# MCU.net
KiCad netlist of a schematic drawn in Altium Designer
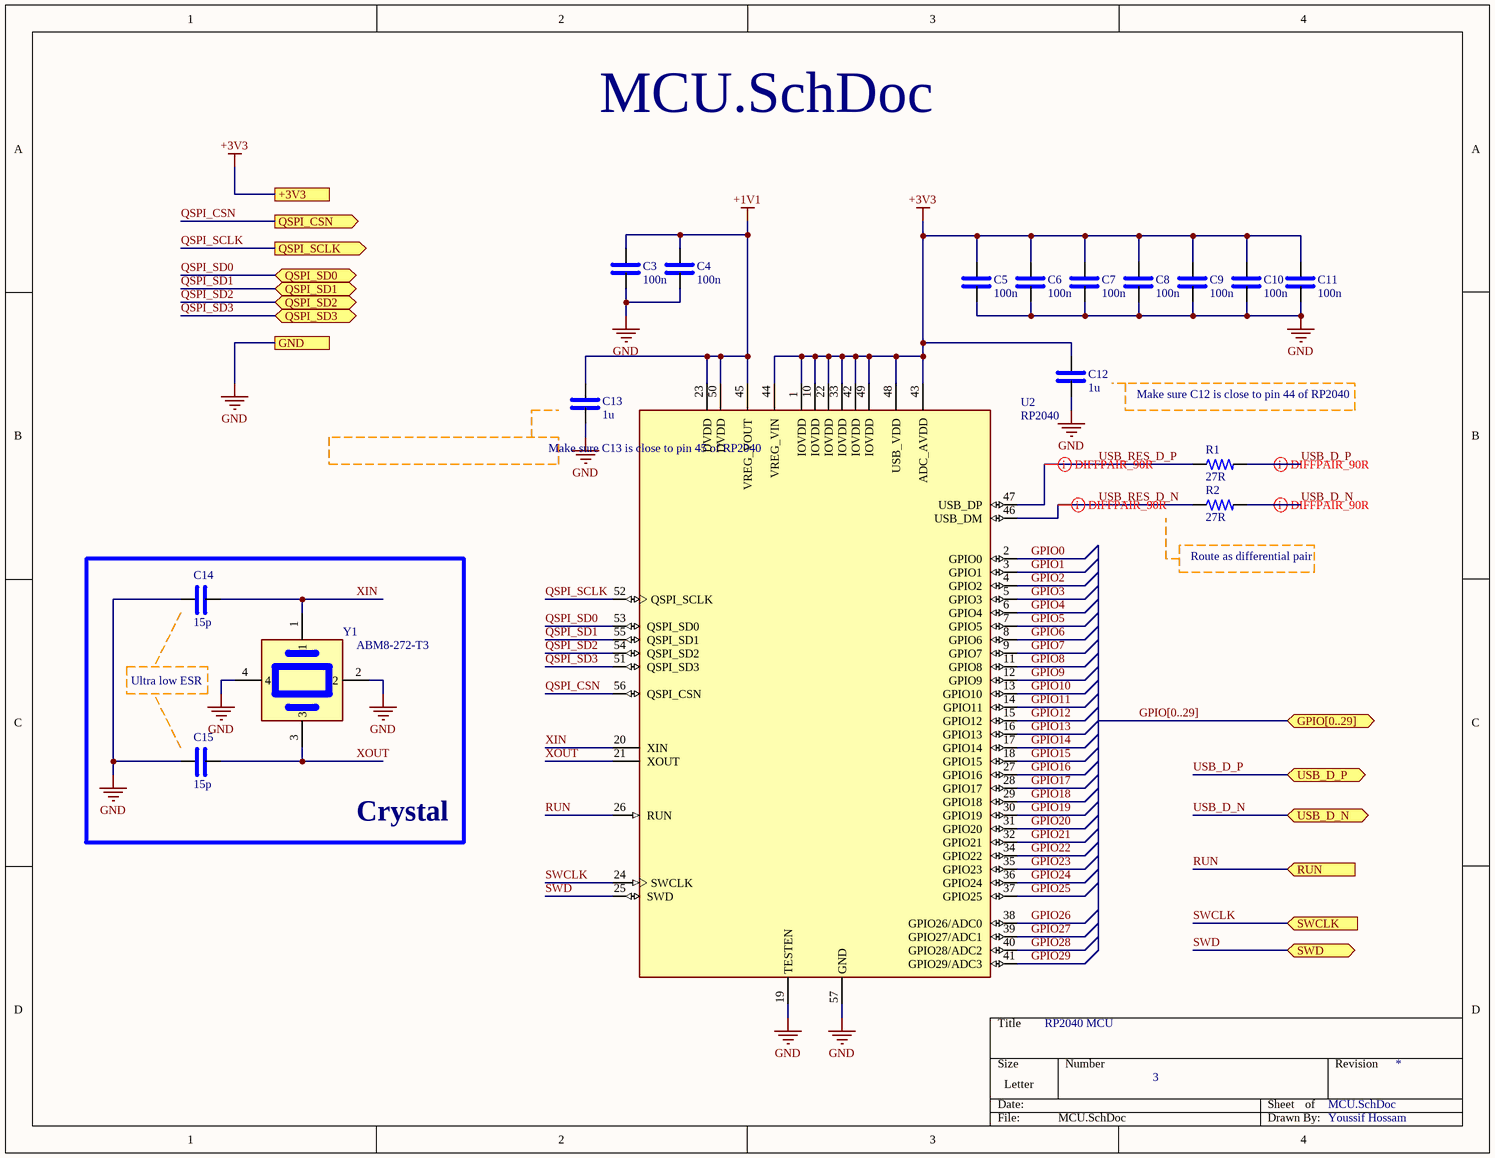
[diagram p0: MCU.SchDoc]

(export (version "E")
  (design (tool "Eeschema 10.0.6"))
  (components
    (comp (ref "C3")
      (value "100n")
      (footprint "0402 CAP")
      (fields
        (field (name "MANUFACTURER") "KEMET")
        (field (name "MANUFACTURER PART NUMBER") "C0805C104K4RACTU")
      )
      (libsource (lib "Integrated_Library") (part "0402 SMD Capacitor"))
    )
    (comp (ref "C4")
      (value "100n")
      (footprint "0402 CAP")
      (fields
        (field (name "MANUFACTURER") "KEMET")
        (field (name "MANUFACTURER PART NUMBER") "C0805C104K4RACTU")
      )
      (libsource (lib "Integrated_Library") (part "0402 SMD Capacitor"))
    )
    (comp (ref "C5")
      (value "100n")
      (footprint "0402 CAP")
      (fields
        (field (name "MANUFACTURER") "KEMET")
        (field (name "MANUFACTURER PART NUMBER") "C0805C104K4RACTU")
      )
      (libsource (lib "Integrated_Library") (part "0402 SMD Capacitor"))
    )
    (comp (ref "C6")
      (value "100n")
      (footprint "0402 CAP")
      (fields
        (field (name "MANUFACTURER") "KEMET")
        (field (name "MANUFACTURER PART NUMBER") "C0805C104K4RACTU")
      )
      (libsource (lib "Integrated_Library") (part "0402 SMD Capacitor"))
    )
    (comp (ref "C7")
      (value "100n")
      (footprint "0402 CAP")
      (fields
        (field (name "MANUFACTURER") "KEMET")
        (field (name "MANUFACTURER PART NUMBER") "C0805C104K4RACTU")
      )
      (libsource (lib "Integrated_Library") (part "0402 SMD Capacitor"))
    )
    (comp (ref "C8")
      (value "100n")
      (footprint "0402 CAP")
      (fields
        (field (name "MANUFACTURER") "KEMET")
        (field (name "MANUFACTURER PART NUMBER") "C0805C104K4RACTU")
      )
      (libsource (lib "Integrated_Library") (part "0402 SMD Capacitor"))
    )
    (comp (ref "C9")
      (value "100n")
      (footprint "0402 CAP")
      (fields
        (field (name "MANUFACTURER") "KEMET")
        (field (name "MANUFACTURER PART NUMBER") "C0805C104K4RACTU")
      )
      (libsource (lib "Integrated_Library") (part "0402 SMD Capacitor"))
    )
    (comp (ref "C10")
      (value "100n")
      (footprint "0402 CAP")
      (fields
        (field (name "MANUFACTURER") "KEMET")
        (field (name "MANUFACTURER PART NUMBER") "C0805C104K4RACTU")
      )
      (libsource (lib "Integrated_Library") (part "0402 SMD Capacitor"))
    )
    (comp (ref "C11")
      (value "100n")
      (footprint "0402 CAP")
      (fields
        (field (name "MANUFACTURER") "KEMET")
        (field (name "MANUFACTURER PART NUMBER") "C0805C104K4RACTU")
      )
      (libsource (lib "Integrated_Library") (part "0402 SMD Capacitor"))
    )
    (comp (ref "C12")
      (value "1u")
      (footprint "0402 CAP")
      (fields
        (field (name "MANUFACTURER") "KEMET")
        (field (name "MANUFACTURER PART NUMBER") "C0805C105K4RACTU")
      )
      (libsource (lib "Integrated_Library") (part "0402 SMD Capacitor"))
    )
    (comp (ref "C13")
      (value "1u")
      (footprint "0402 CAP")
      (fields
        (field (name "MANUFACTURER") "KEMET")
        (field (name "MANUFACTURER PART NUMBER") "C0805C105K4RACTU")
      )
      (libsource (lib "Integrated_Library") (part "0402 SMD Capacitor"))
    )
    (comp (ref "C14")
      (value "15p")
      (footprint "0402 CAP")
      (fields
        (field (name "MANUFACTURER") "Yageo")
        (field (name "MANUFACTURER PART NUMBER") "CC0805FRNPO9BN150")
      )
      (libsource (lib "Integrated_Library") (part "0402 SMD Capacitor"))
    )
    (comp (ref "C15")
      (value "15p")
      (footprint "0402 CAP")
      (fields
        (field (name "MANUFACTURER") "Yageo")
        (field (name "MANUFACTURER PART NUMBER") "CC0805FRNPO9BN150")
      )
      (libsource (lib "Integrated_Library") (part "0402 SMD Capacitor"))
    )
    (comp (ref "R1")
      (value "27R")
      (footprint "0402 RES")
      (description "Fixed Resistor, Thin Film, 0.125W, 27ohm, 150V, 0.1% +/-Tol, 25ppm/Cel, Surface Mount, 0805")
      (fields
        (field (name "MANUFACTURER") "Yageo")
        (field (name "MANUFACTURER PART NUMBER") "RT0805BRD0727RL")
      )
      (libsource (lib "Integrated_Library") (part "0402 SMD Resistor"))
    )
    (comp (ref "R2")
      (value "27R")
      (footprint "0402 RES")
      (description "Fixed Resistor, Thin Film, 0.125W, 27ohm, 150V, 0.1% +/-Tol, 25ppm/Cel, Surface Mount, 0805")
      (fields
        (field (name "MANUFACTURER") "Yageo")
        (field (name "MANUFACTURER PART NUMBER") "RT0805BRD0727RL")
      )
      (libsource (lib "Integrated_Library") (part "0402 SMD Resistor"))
    )
    (comp (ref "U2")
      (value "RP2040")
      (footprint "QFN40P700X700X90-57N")
      (description "RP2040 chip for Raspberry Pi Pico - ARM® Cortex®-M0+ MCU 32-Bit")
      (fields (field (name "MF") "Raspberry Pi"))
      (libsource (lib "Schlib") (part "RP2040"))
    )
    (comp (ref "Y1")
      (value "ABM8-272-T3")
      (footprint "ABM8-272-T3")
      (description "12 MHz Â±30ppm Crystal 10pF 50 Ohms 4-SMD, No Lead")
      (fields (field (name "MF") "ABRACON"))
      (libsource (lib "Integrated_Library") (part "ABM8-272-T3"))
    )
  )
  (nets
    (net (code "1") (name "+1V1") (class "Default")
      (node (ref "C13") (pin "2") (pinfunction "2_2") (pintype "passive"))
      (node (ref "C3") (pin "2") (pinfunction "2_2") (pintype "passive"))
      (node (ref "C4") (pin "2") (pinfunction "2_2") (pintype "passive"))
      (node (ref "U2") (pin "23") (pinfunction "DVDD_23") (pintype "power_in"))
      (node (ref "U2") (pin "45") (pinfunction "VREG_VOUT_45") (pintype "power_in"))
      (node (ref "U2") (pin "50") (pinfunction "DVDD_50") (pintype "power_in"))
    )
    (net (code "2") (name "+3V3") (class "Default")
      (node (ref "C10") (pin "2") (pinfunction "2_2") (pintype "passive"))
      (node (ref "C11") (pin "2") (pinfunction "2_2") (pintype "passive"))
      (node (ref "C12") (pin "2") (pinfunction "2_2") (pintype "passive"))
      (node (ref "C5") (pin "2") (pinfunction "2_2") (pintype "passive"))
      (node (ref "C6") (pin "2") (pinfunction "2_2") (pintype "passive"))
      (node (ref "C7") (pin "2") (pinfunction "2_2") (pintype "passive"))
      (node (ref "C8") (pin "2") (pinfunction "2_2") (pintype "passive"))
      (node (ref "C9") (pin "2") (pinfunction "2_2") (pintype "passive"))
      (node (ref "U2") (pin "1") (pinfunction "IOVDD_1") (pintype "power_in"))
      (node (ref "U2") (pin "10") (pinfunction "IOVDD_10") (pintype "power_in"))
      (node (ref "U2") (pin "22") (pinfunction "IOVDD_22") (pintype "power_in"))
      (node (ref "U2") (pin "33") (pinfunction "IOVDD_33") (pintype "power_in"))
      (node (ref "U2") (pin "42") (pinfunction "IOVDD_42") (pintype "power_in"))
      (node (ref "U2") (pin "43") (pinfunction "ADC_AVDD_43") (pintype "power_in"))
      (node (ref "U2") (pin "44") (pinfunction "VREG_VIN_44") (pintype "power_in"))
      (node (ref "U2") (pin "48") (pinfunction "USB_VDD_48") (pintype "power_in"))
      (node (ref "U2") (pin "49") (pinfunction "IOVDD_49") (pintype "power_in"))
    )
    (net (code "3") (name "/GPIO0") (class "Default")
      (node (ref "U2") (pin "2") (pinfunction "GPIO0_2") (pintype "bidirectional"))
    )
    (net (code "4") (name "/GPIO1") (class "Default")
      (node (ref "U2") (pin "3") (pinfunction "GPIO1_3") (pintype "bidirectional"))
    )
    (net (code "5") (name "/GPIO2") (class "Default")
      (node (ref "U2") (pin "4") (pinfunction "GPIO2_4") (pintype "bidirectional"))
    )
    (net (code "6") (name "/GPIO3") (class "Default")
      (node (ref "U2") (pin "5") (pinfunction "GPIO3_5") (pintype "bidirectional"))
    )
    (net (code "7") (name "/GPIO4") (class "Default")
      (node (ref "U2") (pin "6") (pinfunction "GPIO4_6") (pintype "bidirectional"))
    )
    (net (code "8") (name "/GPIO5") (class "Default")
      (node (ref "U2") (pin "7") (pinfunction "GPIO5_7") (pintype "bidirectional"))
    )
    (net (code "9") (name "/GPIO6") (class "Default")
      (node (ref "U2") (pin "8") (pinfunction "GPIO6_8") (pintype "bidirectional"))
    )
    (net (code "10") (name "/GPIO7") (class "Default")
      (node (ref "U2") (pin "9") (pinfunction "GPIO7_9") (pintype "bidirectional"))
    )
    (net (code "11") (name "/GPIO8") (class "Default")
      (node (ref "U2") (pin "11") (pinfunction "GPIO8_11") (pintype "bidirectional"))
    )
    (net (code "12") (name "/GPIO9") (class "Default")
      (node (ref "U2") (pin "12") (pinfunction "GPIO9_12") (pintype "bidirectional"))
    )
    (net (code "13") (name "/GPIO10") (class "Default")
      (node (ref "U2") (pin "13") (pinfunction "GPIO10_13") (pintype "bidirectional"))
    )
    (net (code "14") (name "/GPIO11") (class "Default")
      (node (ref "U2") (pin "14") (pinfunction "GPIO11_14") (pintype "bidirectional"))
    )
    (net (code "15") (name "/GPIO12") (class "Default")
      (node (ref "U2") (pin "15") (pinfunction "GPIO12_15") (pintype "bidirectional"))
    )
    (net (code "16") (name "/GPIO13") (class "Default")
      (node (ref "U2") (pin "16") (pinfunction "GPIO13_16") (pintype "bidirectional"))
    )
    (net (code "17") (name "/GPIO14") (class "Default")
      (node (ref "U2") (pin "17") (pinfunction "GPIO14_17") (pintype "bidirectional"))
    )
    (net (code "18") (name "/GPIO15") (class "Default")
      (node (ref "U2") (pin "18") (pinfunction "GPIO15_18") (pintype "bidirectional"))
    )
    (net (code "19") (name "/GPIO16") (class "Default")
      (node (ref "U2") (pin "27") (pinfunction "GPIO16_27") (pintype "bidirectional"))
    )
    (net (code "20") (name "/GPIO17") (class "Default")
      (node (ref "U2") (pin "28") (pinfunction "GPIO17_28") (pintype "bidirectional"))
    )
    (net (code "21") (name "/GPIO18") (class "Default")
      (node (ref "U2") (pin "29") (pinfunction "GPIO18_29") (pintype "bidirectional"))
    )
    (net (code "22") (name "/GPIO19") (class "Default")
      (node (ref "U2") (pin "30") (pinfunction "GPIO19_30") (pintype "bidirectional"))
    )
    (net (code "23") (name "/GPIO20") (class "Default")
      (node (ref "U2") (pin "31") (pinfunction "GPIO20_31") (pintype "bidirectional"))
    )
    (net (code "24") (name "/GPIO21") (class "Default")
      (node (ref "U2") (pin "32") (pinfunction "GPIO21_32") (pintype "bidirectional"))
    )
    (net (code "25") (name "/GPIO22") (class "Default")
      (node (ref "U2") (pin "34") (pinfunction "GPIO22_34") (pintype "bidirectional"))
    )
    (net (code "26") (name "/GPIO23") (class "Default")
      (node (ref "U2") (pin "35") (pinfunction "GPIO23_35") (pintype "bidirectional"))
    )
    (net (code "27") (name "/GPIO24") (class "Default")
      (node (ref "U2") (pin "36") (pinfunction "GPIO24_36") (pintype "bidirectional"))
    )
    (net (code "28") (name "/GPIO25") (class "Default")
      (node (ref "U2") (pin "37") (pinfunction "GPIO25_37") (pintype "bidirectional"))
    )
    (net (code "29") (name "/GPIO26") (class "Default")
      (node (ref "U2") (pin "38") (pinfunction "GPIO26/ADC0_38") (pintype "bidirectional"))
    )
    (net (code "30") (name "/GPIO27") (class "Default")
      (node (ref "U2") (pin "39") (pinfunction "GPIO27/ADC1_39") (pintype "bidirectional"))
    )
    (net (code "31") (name "/GPIO28") (class "Default")
      (node (ref "U2") (pin "40") (pinfunction "GPIO28/ADC2_40") (pintype "bidirectional"))
    )
    (net (code "32") (name "/GPIO29") (class "Default")
      (node (ref "U2") (pin "41") (pinfunction "GPIO29/ADC3_41") (pintype "bidirectional"))
    )
    (net (code "34") (name "/QSPI_CSN") (class "Default")
      (node (ref "U2") (pin "56") (pinfunction "QSPI_CSN_56") (pintype "bidirectional"))
    )
    (net (code "35") (name "/QSPI_SCLK") (class "Default")
      (node (ref "U2") (pin "52") (pinfunction "QSPI_SCLK_52") (pintype "bidirectional"))
    )
    (net (code "36") (name "/QSPI_SD0") (class "Default")
      (node (ref "U2") (pin "53") (pinfunction "QSPI_SD0_53") (pintype "bidirectional"))
    )
    (net (code "37") (name "/QSPI_SD1") (class "Default")
      (node (ref "U2") (pin "55") (pinfunction "QSPI_SD1_55") (pintype "bidirectional"))
    )
    (net (code "38") (name "/QSPI_SD2") (class "Default")
      (node (ref "U2") (pin "54") (pinfunction "QSPI_SD2_54") (pintype "bidirectional"))
    )
    (net (code "39") (name "/QSPI_SD3") (class "Default")
      (node (ref "U2") (pin "51") (pinfunction "QSPI_SD3_51") (pintype "bidirectional"))
    )
    (net (code "40") (name "/RUN") (class "Default")
      (node (ref "U2") (pin "26") (pinfunction "RUN_26") (pintype "input"))
    )
    (net (code "41") (name "/SWCLK") (class "Default")
      (node (ref "U2") (pin "24") (pinfunction "SWCLK_24") (pintype "input"))
    )
    (net (code "42") (name "/SWD") (class "Default")
      (node (ref "U2") (pin "25") (pinfunction "SWD_25") (pintype "bidirectional"))
    )
    (net (code "43") (name "/USB_D_N") (class "Default")
      (node (ref "R2") (pin "2") (pinfunction "2_2") (pintype "passive"))
    )
    (net (code "44") (name "/USB_D_P") (class "Default")
      (node (ref "R1") (pin "2") (pinfunction "2_2") (pintype "passive"))
    )
    (net (code "45") (name "/USB_RES_D_N") (class "Default")
      (node (ref "R2") (pin "1") (pinfunction "1_1") (pintype "passive"))
      (node (ref "U2") (pin "46") (pinfunction "USB_DM_46") (pintype "bidirectional"))
    )
    (net (code "46") (name "/USB_RES_D_P") (class "Default")
      (node (ref "R1") (pin "1") (pinfunction "1_1") (pintype "passive"))
      (node (ref "U2") (pin "47") (pinfunction "USB_DP_47") (pintype "bidirectional"))
    )
    (net (code "47") (name "/XIN") (class "Default")
      (node (ref "C14") (pin "1") (pinfunction "1_1") (pintype "passive"))
      (node (ref "U2") (pin "20") (pinfunction "XIN_20") (pintype "passive"))
      (node (ref "Y1") (pin "1") (pinfunction "1_1") (pintype "passive"))
    )
    (net (code "48") (name "/XOUT") (class "Default")
      (node (ref "C15") (pin "1") (pinfunction "1_1") (pintype "passive"))
      (node (ref "U2") (pin "21") (pinfunction "XOUT_21") (pintype "passive"))
      (node (ref "Y1") (pin "3") (pinfunction "3_3") (pintype "passive"))
    )
    (net (code "49") (name "GND") (class "Default")
      (node (ref "C10") (pin "1") (pinfunction "1_1") (pintype "passive"))
      (node (ref "C11") (pin "1") (pinfunction "1_1") (pintype "passive"))
      (node (ref "C12") (pin "1") (pinfunction "1_1") (pintype "passive"))
      (node (ref "C13") (pin "1") (pinfunction "1_1") (pintype "passive"))
      (node (ref "C14") (pin "2") (pinfunction "2_2") (pintype "passive"))
      (node (ref "C15") (pin "2") (pinfunction "2_2") (pintype "passive"))
      (node (ref "C3") (pin "1") (pinfunction "1_1") (pintype "passive"))
      (node (ref "C4") (pin "1") (pinfunction "1_1") (pintype "passive"))
      (node (ref "C5") (pin "1") (pinfunction "1_1") (pintype "passive"))
      (node (ref "C6") (pin "1") (pinfunction "1_1") (pintype "passive"))
      (node (ref "C7") (pin "1") (pinfunction "1_1") (pintype "passive"))
      (node (ref "C8") (pin "1") (pinfunction "1_1") (pintype "passive"))
      (node (ref "C9") (pin "1") (pinfunction "1_1") (pintype "passive"))
      (node (ref "U2") (pin "19") (pinfunction "TESTEN_19") (pintype "passive"))
      (node (ref "U2") (pin "57") (pinfunction "GND_57") (pintype "power_in"))
      (node (ref "Y1") (pin "2") (pinfunction "2_2") (pintype "power_in"))
      (node (ref "Y1") (pin "4") (pinfunction "4_4") (pintype "power_in"))
    )
  )
)
